# schematic.net
KiCad netlist of a schematic drawn in Altium Designer
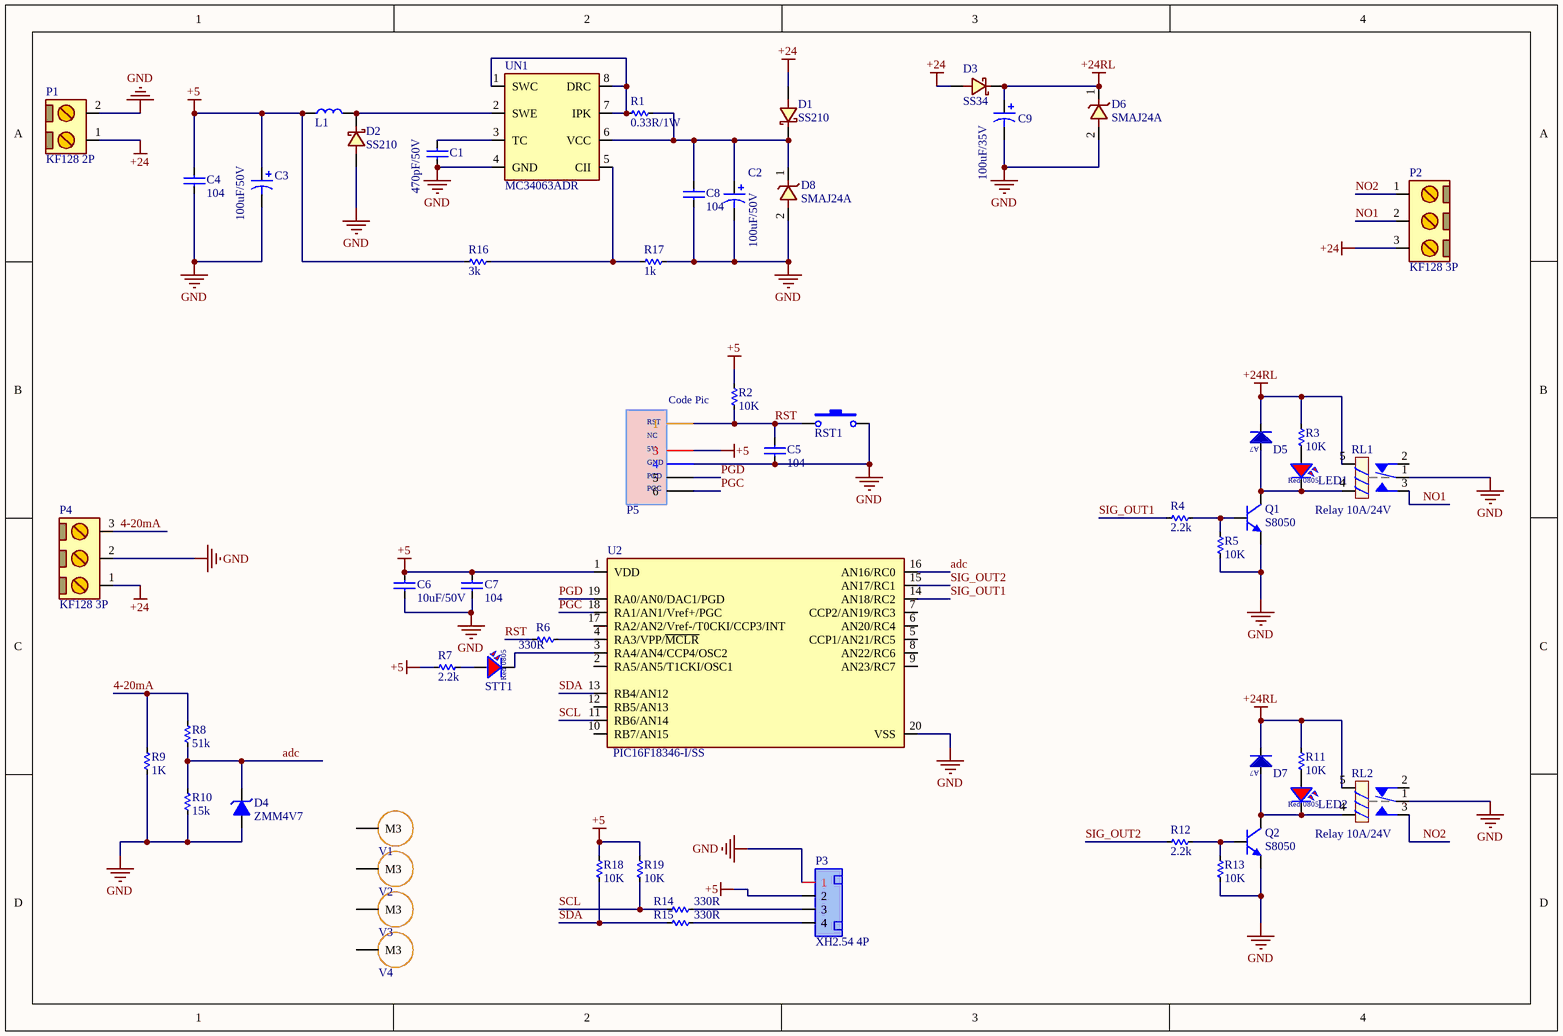
[diagram p0: schematic.SchDoc]

(export (version "E")
  (design (tool "Eeschema 10.0.6"))
  (components
    (comp (ref "C1")
      (value "470pF/50V")
      (footprint "C_0805_SMD")
      (description "Cap SMD 0805  470pF 50V")
      (libsource (lib "RD Integrated_Library") (part "Cap 0805 470pF 50V"))
    )
    (comp (ref "C2")
      (value "100uF/50V")
      (footprint "C_8X12")
      (description "Polarized Capacitor (Axial) 100uF 50V")
      (libsource (lib "RD Integrated_Library") (part "Cap Pol 100uF/50V"))
    )
    (comp (ref "C3")
      (value "100uF/50V")
      (footprint "C_8X12")
      (description "Polarized Capacitor (Axial) 100uF 50V")
      (libsource (lib "RD Integrated_Library") (part "Cap Pol 100uF/50V"))
    )
    (comp (ref "C4")
      (value "104")
      (footprint "C_0805_SMD")
      (description "Cap SMD 0805 104-100nF-0.1uF 50V")
      (libsource (lib "RD Integrated_Library") (part "Cap 0805 104 100nF"))
    )
    (comp (ref "C5")
      (value "104")
      (footprint "C_0805_SMD")
      (description "Cap SMD 0805 104-100nF-0.1uF 50V")
      (libsource (lib "RD Integrated_Library") (part "Cap 0805 104 100nF"))
    )
    (comp (ref "C6")
      (value "10uF/50V")
      (footprint "C_0805_SMD")
      (description "Cap SMD 0805 10uF 50V")
      (libsource (lib "RD Integrated_Library") (part "Cap 0805 10uF 50V"))
    )
    (comp (ref "C7")
      (value "104")
      (footprint "C_0805_SMD")
      (description "Cap SMD 0805 104-100nF-0.1uF 50V")
      (libsource (lib "RD Integrated_Library") (part "Cap 0805 104 100nF"))
    )
    (comp (ref "C8")
      (value "104")
      (footprint "C_0805_SMD")
      (description "Cap SMD 0805 104-100nF-0.1uF 50V")
      (libsource (lib "RD Integrated_Library") (part "Cap 0805 104 100nF"))
    )
    (comp (ref "C9")
      (value "100uF/35V")
      (footprint "C_6.3x12")
      (description "Polarized Capacitor (Axial) 100uF 35V")
      (libsource (lib "RD Integrated_Library") (part "Cap Pol 100uF/35V"))
    )
    (comp (ref "D1")
      (value "SS210")
      (footprint "D_SMA")
      (description "Surface-Mount Schottky Barrier Rectifier")
      (libsource (lib "RD Integrated_Library") (part "SS210-SMA"))
    )
    (comp (ref "D2")
      (value "SS210")
      (footprint "D_SMA")
      (description "Surface-Mount Schottky Barrier Rectifier")
      (libsource (lib "RD Integrated_Library") (part "SS210-SMA"))
    )
    (comp (ref "D3")
      (value "SS34")
      (footprint "D_SMA")
      (description "Surface-Mount Schottky Barrier Rectifier")
      (libsource (lib "RD Integrated_Library") (part "SS34-SMA"))
    )
    (comp (ref "D4")
      (value "ZMM4V7")
      (footprint "SOD80C_MFG")
      (description "zener 4.7V 500mW SMD")
      (fields (field (name "DESIGNED BY") "Nhox"))
      (libsource (lib "RD Integrated_Library") (part "ZMM4V7 Diode Zener"))
    )
    (comp (ref "D5")
      (value "1N4007")
      (footprint "DIODE_SOD123-FL")
      (description "Rectifier diode 1n4007-A7 SOD-123FL")
      (fields (field (name "DESIGNED BY") "TranLuyen"))
      (libsource (lib "RD Integrated_Library") (part "1n4007W-A7-SOD-123FL"))
    )
    (comp (ref "D6")
      (value "SMAJ24A")
      (footprint "DO_241AC_SMA_MFG")
      (description "SMAJ Series 400W Surface Mount Uni-Directional TVS Diode - DO-214AC")
      (fields (field (name "DESIGNED BY") "TranLuyen"))
      (libsource (lib "RD Integrated_Library") (part "TVS SMAJ24A-DO241AC"))
    )
    (comp (ref "D7")
      (value "1N4007")
      (footprint "DIODE_SOD123-FL")
      (description "Rectifier diode 1n4007-A7 SOD-123FL")
      (fields (field (name "DESIGNED BY") "TranLuyen"))
      (libsource (lib "RD Integrated_Library") (part "1n4007W-A7-SOD-123FL"))
    )
    (comp (ref "D8")
      (value "SMAJ24A")
      (footprint "DO_241AC_SMA_MFG")
      (description "SMAJ Series 400W Surface Mount Uni-Directional TVS Diode - DO-214AC")
      (fields (field (name "DESIGNED BY") "TranLuyen"))
      (libsource (lib "RD Integrated_Library") (part "TVS SMAJ24A-DO241AC"))
    )
    (comp (ref "L1")
      (value "220uH")
      (footprint "CDRH127")
      (description "CDRH127 size 12 x 12 x 8mm")
      (fields (field (name "DESIGNED BY") "TranLuyen"))
      (libsource (lib "RD Integrated_Library") (part "IND 1280-221 220uH 1.9A"))
    )
    (comp (ref "LED1")
      (value "LED RED")
      (footprint "LED 0805 Red")
      (description "LED 0805 SMD RED")
      (fields (field (name "DESIGNED BY") "TranLuyen"))
      (libsource (lib "RD Integrated_Library") (part "LED 0805 RED"))
    )
    (comp (ref "LED2")
      (value "LED RED")
      (footprint "LED 0805 Red")
      (description "LED 0805 SMD RED")
      (fields (field (name "DESIGNED BY") "TranLuyen"))
      (libsource (lib "RD Integrated_Library") (part "LED 0805 RED"))
    )
    (comp (ref "P1")
      (value "KF128 2P")
      (footprint "KF128 5.08 2P")
      (description "Header, 2-Pin, Medium KF128 2P-5.08mm")
      (fields (field (name "DESIGNED BY") "TranLuyen"))
      (libsource (lib "RD Integrated_Library") (part "KF128-5.08-2P-5.08mm"))
    )
    (comp (ref "P2")
      (value "KF128 3P")
      (footprint "KF128 5.08 3P")
      (description "Header, 3-Pin, Medium KF128 3P-5.08mm")
      (fields (field (name "DESIGNED BY") "TranLuyen"))
      (libsource (lib "") (part "KF128-5.08-3P-5.08mm_1"))
    )
    (comp (ref "P3")
      (value "XH2.54 4P")
      (footprint "XH2.54_4P_RA")
      (description "XH2.54 RA")
      (libsource (lib "RD Integrated_Library") (part "XH2.54_4P_RA"))
    )
    (comp (ref "P4")
      (value "KF128 3P")
      (footprint "KF128 5.08 3P")
      (description "Header, 3-Pin, Medium KF128 3P-5.08mm")
      (fields (field (name "DESIGNED BY") "TranLuyen"))
      (libsource (lib "RD Integrated_Library") (part "KF128-5.08-3P-5.08mm"))
    )
    (comp (ref "P5")
      (value "HDR 6 Male")
      (footprint "Header Code Pic 2.54 6P")
      (description "Header 6-5Pin")
      (libsource (lib "RD Integrated_Library") (part "Header Code PIC"))
    )
    (comp (ref "Q1")
      (value "S8050")
      (footprint "SOT23_N NXP")
      (description "J3Y-NPN SMD Transistor SOT23")
      (libsource (lib "RD Integrated_Library") (part "S8050 SOT-23"))
    )
    (comp (ref "Q2")
      (value "S8050")
      (footprint "SOT23_N NXP")
      (description "J3Y-NPN SMD Transistor SOT23")
      (libsource (lib "RD Integrated_Library") (part "S8050 SOT-23"))
    )
    (comp (ref "R1")
      (value "0.33R/1W")
      (footprint "RES-SMD-2512")
      (description "Resistor SMD 2512 1W")
      (libsource (lib "RD Integrated_Library") (part "Res 0.33R 2512 1W"))
    )
    (comp (ref "R2")
      (value "10K")
      (footprint "RES-SMD-0805")
      (description "Resistor SMD 0805")
      (libsource (lib "RD Integrated_Library") (part "Res 10k 0805"))
    )
    (comp (ref "R3")
      (value "10K")
      (footprint "RES-SMD-0805")
      (description "Resistor SMD 0805")
      (libsource (lib "RD Integrated_Library") (part "Res 10k 0805"))
    )
    (comp (ref "R4")
      (value "2.2k")
      (footprint "RES-SMD-0805")
      (description "Resistor SMD 0805")
      (libsource (lib "RD Integrated_Library") (part "Res 2.2K 0805"))
    )
    (comp (ref "R5")
      (value "10K")
      (footprint "RES-SMD-0805")
      (description "Resistor SMD 0805")
      (libsource (lib "RD Integrated_Library") (part "Res 10k 0805"))
    )
    (comp (ref "R6")
      (value "330R")
      (footprint "RES-SMD-0805")
      (description "Resistor SMD 0805")
      (libsource (lib "RD Integrated_Library") (part "Res 330R 0805"))
    )
    (comp (ref "R7")
      (value "2.2k")
      (footprint "RES-SMD-0805")
      (description "Resistor SMD 0805")
      (libsource (lib "RD Integrated_Library") (part "Res 2.2K 0805"))
    )
    (comp (ref "R8")
      (value "51k")
      (footprint "RES-SMD-0805")
      (description "Resistor SMD 0805")
      (libsource (lib "RD Integrated_Library") (part "Res 51K 0805"))
    )
    (comp (ref "R9")
      (value "1K")
      (footprint "RES-SMD-2512")
      (description "RES 2512 1W")
      (libsource (lib "RD Integrated_Library") (part "Res 1K 2512"))
    )
    (comp (ref "R10")
      (value "15k")
      (footprint "RES-SMD-0805")
      (description "Resistor SMD 0805")
      (libsource (lib "RD Integrated_Library") (part "Res 15K 0805"))
    )
    (comp (ref "R11")
      (value "10K")
      (footprint "RES-SMD-0805")
      (description "Resistor SMD 0805")
      (libsource (lib "RD Integrated_Library") (part "Res 10k 0805"))
    )
    (comp (ref "R12")
      (value "2.2k")
      (footprint "RES-SMD-0805")
      (description "Resistor SMD 0805")
      (libsource (lib "RD Integrated_Library") (part "Res 2.2K 0805"))
    )
    (comp (ref "R13")
      (value "10K")
      (footprint "RES-SMD-0805")
      (description "Resistor SMD 0805")
      (libsource (lib "RD Integrated_Library") (part "Res 10k 0805"))
    )
    (comp (ref "R14")
      (value "330R")
      (footprint "RES-SMD-0805")
      (description "Resistor SMD 0805")
      (libsource (lib "RD Integrated_Library") (part "Res 330R 0805"))
    )
    (comp (ref "R15")
      (value "330R")
      (footprint "RES-SMD-0805")
      (description "Resistor SMD 0805")
      (libsource (lib "RD Integrated_Library") (part "Res 330R 0805"))
    )
    (comp (ref "R16")
      (value "3k")
      (footprint "RES-SMD-0805")
      (description "Resistor SMD 0805")
      (fields (field (name "DESIGNED BY") "TranLuyen"))
      (libsource (lib "RD Integrated_Library") (part "Res 3k 0805"))
    )
    (comp (ref "R17")
      (value "1k")
      (footprint "RES-SMD-0805")
      (description "Resistor SMD 0805")
      (libsource (lib "RD Integrated_Library") (part "Res 1k 0805"))
    )
    (comp (ref "R18")
      (value "10K")
      (footprint "RES-SMD-0805")
      (description "Resistor SMD 0805")
      (libsource (lib "RD Integrated_Library") (part "Res 10k 0805"))
    )
    (comp (ref "R19")
      (value "10K")
      (footprint "RES-SMD-0805")
      (description "Resistor SMD 0805")
      (libsource (lib "RD Integrated_Library") (part "Res 10k 0805"))
    )
    (comp (ref "RL1")
      (value "Relay 10A/24V")
      (footprint "Relay 5 pin 10A")
      (description "Relay SPDT,10A - 24VDC 5 Pin SONGLE SLC")
      (libsource (lib "RD Integrated_Library") (part "Relay 24V 5 Pin 10A SLC"))
    )
    (comp (ref "RL2")
      (value "Relay 10A/24V")
      (footprint "Relay 5 pin 10A")
      (description "Relay SPDT,10A - 24VDC 5 Pin SONGLE SLC")
      (libsource (lib "RD Integrated_Library") (part "Relay 24V 5 Pin 10A SLC"))
    )
    (comp (ref "RST1")
      (value "SW-SMD")
      (footprint "SW-SMD 3x6 mm")
      (description "Button 3x6 mm x 2.5mm 2Pin SMD")
      (libsource (lib "RD Integrated_Library") (part "SW2 SMD 3x6"))
    )
    (comp (ref "STT1")
      (value "LED RED")
      (footprint "LED 0805 Red")
      (description "LED 0805 SMD RED")
      (fields (field (name "DESIGNED BY") "TranLuyen"))
      (libsource (lib "RD Integrated_Library") (part "LED 0805 RED"))
    )
    (comp (ref "U2")
      (value "PIC16F18346-I/SS")
      (footprint "SOG65_20_W")
      (description "IC MCU 8BIT 28KB FLASH 20SSOP")
      (libsource (lib "RD Integrated_Library") (part "PIC16F18346-I/SS"))
    )
    (comp (ref "UN1")
      (value "MC34063ADR")
      (footprint "SO_8")
      (description "MC3x063A 1.5-A Peak Boost/Buck/Inverting Switching Regulators")
      (fields (field (name "DESIGNED BY") "TranLuyen"))
      (libsource (lib "RD Integrated_Library") (part "MC34063ADR"))
    )
    (comp (ref "V1")
      (value "Vit m3")
      (footprint "Screw M3x5 - Via")
      (description "Screw Vit m3")
      (libsource (lib "RD Integrated_Library") (part "Screw Vit m3"))
    )
    (comp (ref "V2")
      (value "Vit m3")
      (footprint "Screw M3x5 - Via")
      (description "Screw Vit m3")
      (libsource (lib "RD Integrated_Library") (part "Screw Vit m3"))
    )
    (comp (ref "V3")
      (value "Vit m3")
      (footprint "Screw M3x5 - Via")
      (description "Screw Vit m3")
      (libsource (lib "RD Integrated_Library") (part "Screw Vit m3"))
    )
    (comp (ref "V4")
      (value "Vit m3")
      (footprint "Screw M3x5 - Via")
      (description "Screw Vit m3")
      (libsource (lib "RD Integrated_Library") (part "Screw Vit m3"))
    )
  )
  (nets
    (net (code "1") (name "+5") (class "Default")
      (node (ref "C3") (pin "1") (pinfunction "1_1") (pintype "passive"))
      (node (ref "C4") (pin "2") (pinfunction "2_2") (pintype "passive"))
      (node (ref "C6") (pin "2") (pinfunction "2_2") (pintype "passive"))
      (node (ref "C7") (pin "2") (pinfunction "2_2") (pintype "passive"))
      (node (ref "L1") (pin "1") (pinfunction "1_1") (pintype "passive"))
      (node (ref "P3") (pin "2") (pinfunction "2_2") (pintype "passive"))
      (node (ref "P5") (pin "3") (pinfunction "3_3") (pintype "passive"))
      (node (ref "R16") (pin "2") (pinfunction "2_2") (pintype "passive"))
      (node (ref "R18") (pin "1") (pinfunction "1_1") (pintype "passive"))
      (node (ref "R19") (pin "1") (pinfunction "1_1") (pintype "passive"))
      (node (ref "R2") (pin "1") (pinfunction "1_1") (pintype "passive"))
      (node (ref "R7") (pin "2") (pinfunction "2_2") (pintype "passive"))
      (node (ref "U2") (pin "1") (pinfunction "VDD_1") (pintype "passive"))
    )
    (net (code "2") (name "+24") (class "Default")
      (node (ref "D1") (pin "1") (pinfunction "A_1") (pintype "passive"))
      (node (ref "D3") (pin "1") (pinfunction "A_1") (pintype "passive"))
      (node (ref "P1") (pin "1") (pinfunction "1_1") (pintype "passive"))
      (node (ref "P2") (pin "3") (pinfunction "3_3") (pintype "passive"))
      (node (ref "P4") (pin "1") (pinfunction "1_1") (pintype "passive"))
    )
    (net (code "3") (name "+24RL") (class "Default")
      (node (ref "C9") (pin "1") (pinfunction "1_1") (pintype "passive"))
      (node (ref "D3") (pin "2") (pinfunction "K_2") (pintype "passive"))
      (node (ref "D5") (pin "K") (pinfunction "K_K") (pintype "passive"))
      (node (ref "D6") (pin "1") (pinfunction "1_1") (pintype "passive"))
      (node (ref "D7") (pin "K") (pinfunction "K_K") (pintype "passive"))
      (node (ref "R11") (pin "1") (pinfunction "1_1") (pintype "passive"))
      (node (ref "R3") (pin "1") (pinfunction "1_1") (pintype "passive"))
      (node (ref "RL1") (pin "5") (pinfunction "5_5") (pintype "passive"))
      (node (ref "RL2") (pin "5") (pinfunction "5_5") (pintype "passive"))
    )
    (net (code "4") (name "/4-20mA") (class "Default")
      (node (ref "P4") (pin "3") (pinfunction "3_3") (pintype "passive"))
      (node (ref "R8") (pin "1") (pinfunction "1_1") (pintype "passive"))
      (node (ref "R9") (pin "2") (pinfunction "2_2") (pintype "passive"))
    )
    (net (code "5") (name "/NO1") (class "Default")
      (node (ref "P2") (pin "2") (pinfunction "2_2") (pintype "passive"))
      (node (ref "RL1") (pin "3") (pinfunction "3_3") (pintype "passive"))
    )
    (net (code "6") (name "/NO2") (class "Default")
      (node (ref "P2") (pin "1") (pinfunction "1_1") (pintype "passive"))
      (node (ref "RL2") (pin "3") (pinfunction "3_3") (pintype "passive"))
    )
    (net (code "7") (name "/PGC") (class "Default")
      (node (ref "P5") (pin "6") (pinfunction "6_6") (pintype "passive"))
      (node (ref "U2") (pin "18") (pinfunction "RA1/AN1/Vref+/PGC_18") (pintype "passive"))
    )
    (net (code "8") (name "/PGD") (class "Default")
      (node (ref "P5") (pin "5") (pinfunction "5_5") (pintype "passive"))
      (node (ref "U2") (pin "19") (pinfunction "RA0/AN0/DAC1/PGD_19") (pintype "passive"))
    )
    (net (code "9") (name "/RST") (class "Default")
      (node (ref "C5") (pin "2") (pinfunction "2_2") (pintype "passive"))
      (node (ref "P5") (pin "1") (pinfunction "1_1") (pintype "passive"))
      (node (ref "R2") (pin "2") (pinfunction "2_2") (pintype "passive"))
      (node (ref "R6") (pin "2") (pinfunction "2_2") (pintype "passive"))
      (node (ref "RST1") (pin "1") (pinfunction "1_1") (pintype "passive"))
    )
    (net (code "10") (name "/SCL") (class "Default")
      (node (ref "R14") (pin "2") (pinfunction "2_2") (pintype "passive"))
      (node (ref "R19") (pin "2") (pinfunction "2_2") (pintype "passive"))
      (node (ref "U2") (pin "11") (pinfunction "RB6/AN14_11") (pintype "passive"))
    )
    (net (code "11") (name "/SDA") (class "Default")
      (node (ref "R15") (pin "2") (pinfunction "2_2") (pintype "passive"))
      (node (ref "R18") (pin "2") (pinfunction "2_2") (pintype "passive"))
      (node (ref "U2") (pin "13") (pinfunction "RB4/AN12_13") (pintype "passive"))
    )
    (net (code "12") (name "/SIG_OUT1") (class "Default")
      (node (ref "R4") (pin "2") (pinfunction "2_2") (pintype "passive"))
      (node (ref "U2") (pin "14") (pinfunction "AN18/RC2_14") (pintype "passive"))
    )
    (net (code "13") (name "/SIG_OUT2") (class "Default")
      (node (ref "R12") (pin "2") (pinfunction "2_2") (pintype "passive"))
      (node (ref "U2") (pin "15") (pinfunction "AN17/RC1_15") (pintype "passive"))
    )
    (net (code "14") (name "/adc") (class "Default")
      (node (ref "D4") (pin "1") (pinfunction "K_1") (pintype "passive"))
      (node (ref "R10") (pin "1") (pinfunction "1_1") (pintype "passive"))
      (node (ref "R8") (pin "2") (pinfunction "2_2") (pintype "passive"))
      (node (ref "U2") (pin "16") (pinfunction "AN16/RC0_16") (pintype "passive"))
    )
    (net (code "15") (name "GND") (class "Default")
      (node (ref "C1") (pin "1") (pinfunction "1_1") (pintype "passive"))
      (node (ref "C2") (pin "2") (pinfunction "2_2") (pintype "passive"))
      (node (ref "C3") (pin "2") (pinfunction "2_2") (pintype "passive"))
      (node (ref "C4") (pin "1") (pinfunction "1_1") (pintype "passive"))
      (node (ref "C5") (pin "1") (pinfunction "1_1") (pintype "passive"))
      (node (ref "C6") (pin "1") (pinfunction "1_1") (pintype "passive"))
      (node (ref "C7") (pin "1") (pinfunction "1_1") (pintype "passive"))
      (node (ref "C8") (pin "1") (pinfunction "1_1") (pintype "passive"))
      (node (ref "C9") (pin "2") (pinfunction "2_2") (pintype "passive"))
      (node (ref "D2") (pin "1") (pinfunction "A_1") (pintype "passive"))
      (node (ref "D4") (pin "2") (pinfunction "A_2") (pintype "passive"))
      (node (ref "D6") (pin "2") (pinfunction "2_2") (pintype "passive"))
      (node (ref "D8") (pin "2") (pinfunction "2_2") (pintype "passive"))
      (node (ref "P1") (pin "2") (pinfunction "2_2") (pintype "passive"))
      (node (ref "P3") (pin "1") (pinfunction "1_1") (pintype "passive"))
      (node (ref "P4") (pin "2") (pinfunction "2_2") (pintype "passive"))
      (node (ref "P5") (pin "4") (pinfunction "4_4") (pintype "passive"))
      (node (ref "Q1") (pin "2") (pinfunction "E_2") (pintype "passive"))
      (node (ref "Q2") (pin "2") (pinfunction "E_2") (pintype "passive"))
      (node (ref "R10") (pin "2") (pinfunction "2_2") (pintype "passive"))
      (node (ref "R13") (pin "2") (pinfunction "2_2") (pintype "passive"))
      (node (ref "R17") (pin "2") (pinfunction "2_2") (pintype "passive"))
      (node (ref "R5") (pin "2") (pinfunction "2_2") (pintype "passive"))
      (node (ref "R9") (pin "1") (pinfunction "1_1") (pintype "passive"))
      (node (ref "RL1") (pin "1") (pinfunction "1_1") (pintype "passive"))
      (node (ref "RL2") (pin "1") (pinfunction "1_1") (pintype "passive"))
      (node (ref "RST1") (pin "2") (pinfunction "2_2") (pintype "passive"))
      (node (ref "U2") (pin "20") (pinfunction "VSS_20") (pintype "passive"))
      (node (ref "UN1") (pin "4") (pinfunction "GND_4") (pintype "passive"))
    )
    (net (code "16") (name "Net-(D1-K)") (class "Default")
      (node (ref "C2") (pin "1") (pinfunction "1_1") (pintype "passive"))
      (node (ref "C8") (pin "2") (pinfunction "2_2") (pintype "passive"))
      (node (ref "D1") (pin "2") (pinfunction "K_2") (pintype "passive"))
      (node (ref "D8") (pin "1") (pinfunction "1_1") (pintype "passive"))
      (node (ref "R1") (pin "1") (pinfunction "1_1") (pintype "passive"))
      (node (ref "UN1") (pin "6") (pinfunction "VCC_6") (pintype "passive"))
    )
    (net (code "17") (name "Net-(D2-K)") (class "Default")
      (node (ref "D2") (pin "2") (pinfunction "K_2") (pintype "passive"))
      (node (ref "L1") (pin "2") (pinfunction "2_2") (pintype "passive"))
      (node (ref "UN1") (pin "2") (pinfunction "SWE_2") (pintype "passive"))
    )
    (net (code "18") (name "Net-(LED1-Pad1)") (class "Default")
      (node (ref "LED1") (pin "1") (pinfunction "1_1") (pintype "passive"))
      (node (ref "R3") (pin "2") (pinfunction "2_2") (pintype "passive"))
    )
    (net (code "19") (name "Net-(LED2-Pad1)") (class "Default")
      (node (ref "LED2") (pin "1") (pinfunction "1_1") (pintype "passive"))
      (node (ref "R11") (pin "2") (pinfunction "2_2") (pintype "passive"))
    )
    (net (code "20") (name "Net-(P3-Pad3)") (class "Default")
      (node (ref "P3") (pin "3") (pinfunction "3_3") (pintype "passive"))
      (node (ref "R14") (pin "1") (pinfunction "1_1") (pintype "passive"))
    )
    (net (code "21") (name "Net-(P3-Pad4)") (class "Default")
      (node (ref "P3") (pin "4") (pinfunction "4_4") (pintype "passive"))
      (node (ref "R15") (pin "1") (pinfunction "1_1") (pintype "passive"))
    )
    (net (code "22") (name "Net-(Q1-B)") (class "Default")
      (node (ref "Q1") (pin "1") (pinfunction "B_1") (pintype "passive"))
      (node (ref "R4") (pin "1") (pinfunction "1_1") (pintype "passive"))
      (node (ref "R5") (pin "1") (pinfunction "1_1") (pintype "passive"))
    )
    (net (code "23") (name "Net-(Q1-C)") (class "Default")
      (node (ref "D5") (pin "A") (pinfunction "A_A") (pintype "passive"))
      (node (ref "LED1") (pin "2") (pinfunction "2_2") (pintype "passive"))
      (node (ref "Q1") (pin "3") (pinfunction "C_3") (pintype "passive"))
      (node (ref "RL1") (pin "4") (pinfunction "4_4") (pintype "passive"))
    )
    (net (code "24") (name "Net-(Q2-B)") (class "Default")
      (node (ref "Q2") (pin "1") (pinfunction "B_1") (pintype "passive"))
      (node (ref "R12") (pin "1") (pinfunction "1_1") (pintype "passive"))
      (node (ref "R13") (pin "1") (pinfunction "1_1") (pintype "passive"))
    )
    (net (code "25") (name "Net-(Q2-C)") (class "Default")
      (node (ref "D7") (pin "A") (pinfunction "A_A") (pintype "passive"))
      (node (ref "LED2") (pin "2") (pinfunction "2_2") (pintype "passive"))
      (node (ref "Q2") (pin "3") (pinfunction "C_3") (pintype "passive"))
      (node (ref "RL2") (pin "4") (pinfunction "4_4") (pintype "passive"))
    )
    (net (code "26") (name "Net-(R7-Pad1)") (class "Default")
      (node (ref "R7") (pin "1") (pinfunction "1_1") (pintype "passive"))
      (node (ref "STT1") (pin "1") (pinfunction "1_1") (pintype "passive"))
    )
    (net (code "27") (name "Net-(U2-RA3{slash}VPP{slash}~{MCLR})") (class "Default")
      (node (ref "R6") (pin "1") (pinfunction "1_1") (pintype "passive"))
      (node (ref "U2") (pin "4") (pinfunction "RA3/VPP/~{MCLR}_4") (pintype "passive"))
    )
    (net (code "28") (name "Net-(U2-RA4{slash}AN4{slash}CCP4{slash}OSC2)") (class "Default")
      (node (ref "STT1") (pin "2") (pinfunction "2_2") (pintype "passive"))
      (node (ref "U2") (pin "3") (pinfunction "RA4/AN4/CCP4/OSC2_3") (pintype "passive"))
    )
    (net (code "29") (name "Net-(UN1-CII)") (class "Default")
      (node (ref "R16") (pin "1") (pinfunction "1_1") (pintype "passive"))
      (node (ref "R17") (pin "1") (pinfunction "1_1") (pintype "passive"))
      (node (ref "UN1") (pin "5") (pinfunction "CII_5") (pintype "passive"))
    )
    (net (code "30") (name "Net-(UN1-DRC)") (class "Default")
      (node (ref "R1") (pin "2") (pinfunction "2_2") (pintype "passive"))
      (node (ref "UN1") (pin "1") (pinfunction "SWC_1") (pintype "passive"))
      (node (ref "UN1") (pin "7") (pinfunction "IPK_7") (pintype "passive"))
      (node (ref "UN1") (pin "8") (pinfunction "DRC_8") (pintype "passive"))
    )
    (net (code "31") (name "Net-(UN1-TC)") (class "Default")
      (node (ref "C1") (pin "2") (pinfunction "2_2") (pintype "passive"))
      (node (ref "UN1") (pin "3") (pinfunction "TC_3") (pintype "passive"))
    )
    (net (code "32") (name "unconnected-(RL1-Pad2)") (class "Default")
      (node (ref "RL1") (pin "2") (pinfunction "2_2") (pintype "passive"))
    )
    (net (code "33") (name "unconnected-(RL2-Pad2)") (class "Default")
      (node (ref "RL2") (pin "2") (pinfunction "2_2") (pintype "passive"))
    )
    (net (code "34") (name "unconnected-(U2-AN20{slash}RC4-Pad6)") (class "Default")
      (node (ref "U2") (pin "6") (pinfunction "AN20/RC4_6") (pintype "passive"))
    )
    (net (code "35") (name "unconnected-(U2-AN22{slash}RC6-Pad8)") (class "Default")
      (node (ref "U2") (pin "8") (pinfunction "AN22/RC6_8") (pintype "passive"))
    )
    (net (code "36") (name "unconnected-(U2-AN23{slash}RC7-Pad9)") (class "Default")
      (node (ref "U2") (pin "9") (pinfunction "AN23/RC7_9") (pintype "passive"))
    )
    (net (code "37") (name "unconnected-(U2-CCP1{slash}AN21{slash}RC5-Pad5)") (class "Default")
      (node (ref "U2") (pin "5") (pinfunction "CCP1/AN21/RC5_5") (pintype "passive"))
    )
    (net (code "38") (name "unconnected-(U2-CCP2{slash}AN19{slash}RC3-Pad7)") (class "Default")
      (node (ref "U2") (pin "7") (pinfunction "CCP2/AN19/RC3_7") (pintype "passive"))
    )
    (net (code "39") (name "unconnected-(U2-RA2{slash}AN2{slash}Vref-{slash}T0CKI{slash}CCP3{slash}INT-Pad17)") (class "Default")
      (node (ref "U2") (pin "17") (pinfunction "RA2/AN2/Vref-/T0CKI/CCP3/INT_17") (pintype "passive"))
    )
    (net (code "40") (name "unconnected-(U2-RA5{slash}AN5{slash}T1CKI{slash}OSC1-Pad2)") (class "Default")
      (node (ref "U2") (pin "2") (pinfunction "RA5/AN5/T1CKI/OSC1_2") (pintype "passive"))
    )
    (net (code "41") (name "unconnected-(U2-RB5{slash}AN13-Pad12)") (class "Default")
      (node (ref "U2") (pin "12") (pinfunction "RB5/AN13_12") (pintype "passive"))
    )
    (net (code "42") (name "unconnected-(U2-RB7{slash}AN15-Pad10)") (class "Default")
      (node (ref "U2") (pin "10") (pinfunction "RB7/AN15_10") (pintype "passive"))
    )
    (net (code "43") (name "unconnected-(V1-M3-Pad1)") (class "Default")
      (node (ref "V1") (pin "1") (pinfunction "M3_1") (pintype "passive"))
    )
    (net (code "44") (name "unconnected-(V2-M3-Pad1)") (class "Default")
      (node (ref "V2") (pin "1") (pinfunction "M3_1") (pintype "passive"))
    )
    (net (code "45") (name "unconnected-(V3-M3-Pad1)") (class "Default")
      (node (ref "V3") (pin "1") (pinfunction "M3_1") (pintype "passive"))
    )
    (net (code "46") (name "unconnected-(V4-M3-Pad1)") (class "Default")
      (node (ref "V4") (pin "1") (pinfunction "M3_1") (pintype "passive"))
    )
  )
)
